# SCH_PCB-device_2024-08-05.net
KiCad netlist of a schematic drawn in EasyEDA
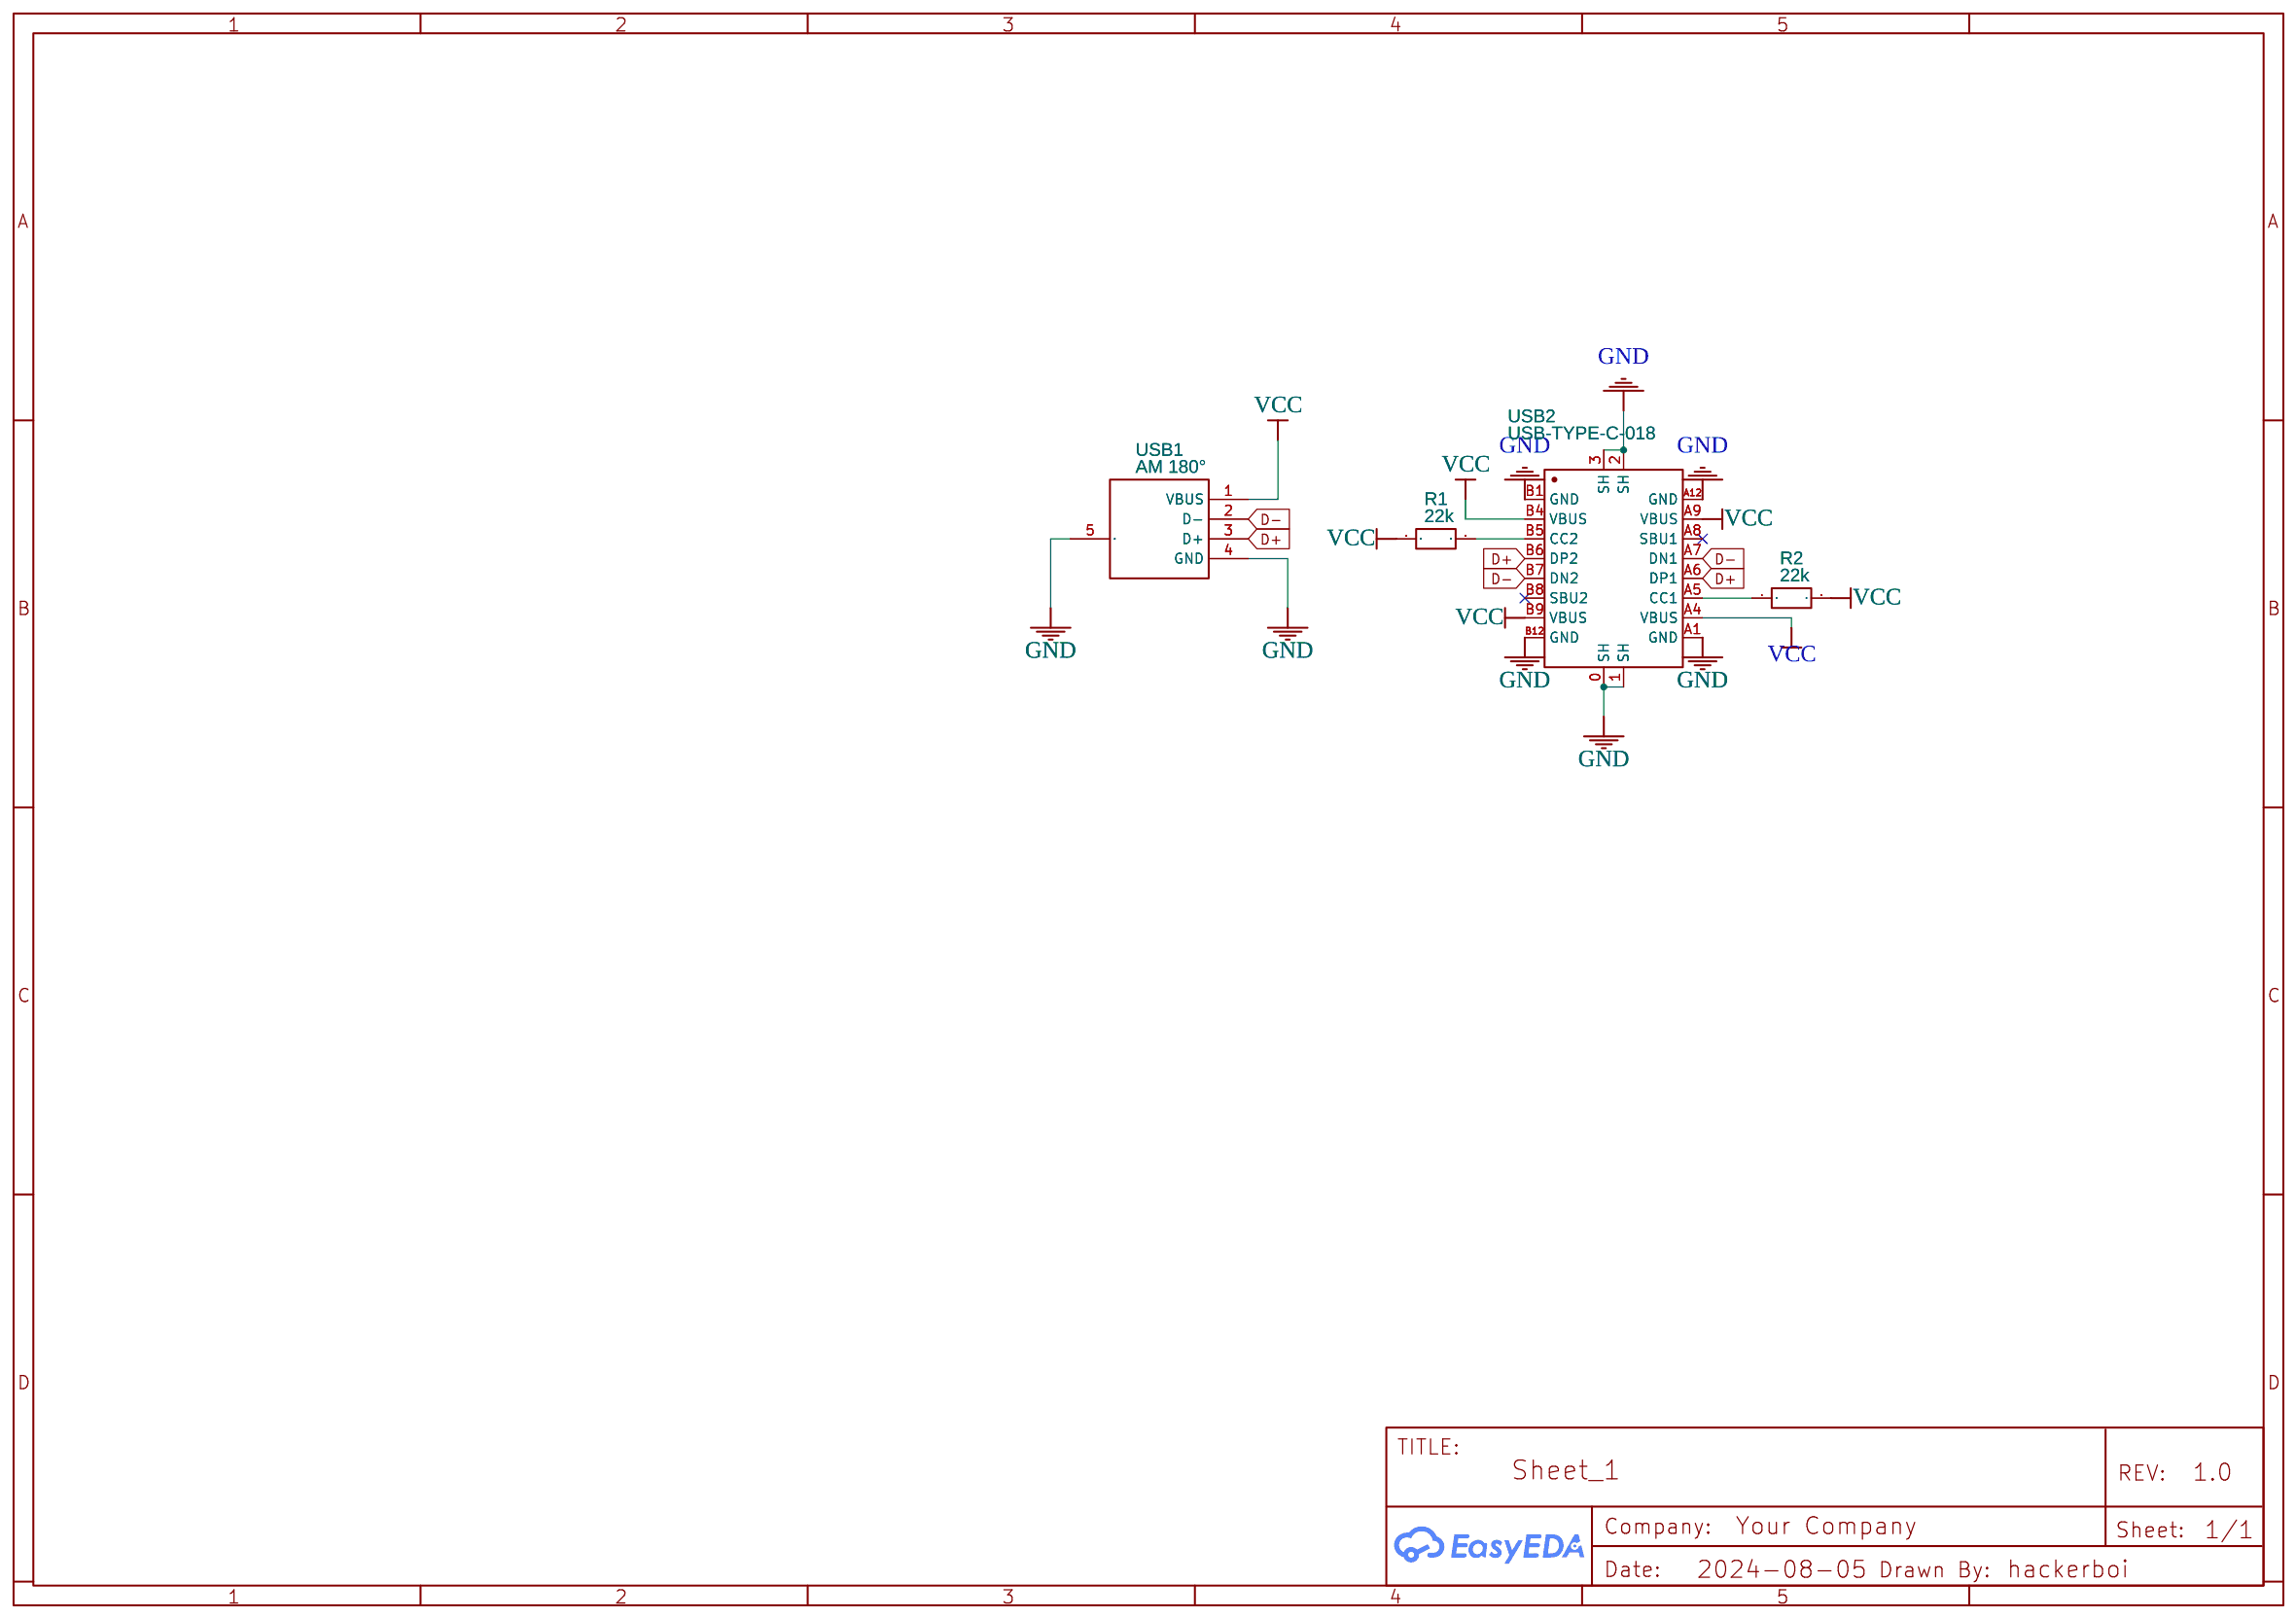
[diagram p0: schematic sheet]

(export (version "E")
  (design (tool "Eeschema 10.0.6"))
  (components
    (comp (ref "R1") (value "22k") (libsource (lib "") (part "R_0603_EU")))
    (comp (ref "R2") (value "22k") (libsource (lib "") (part "R_0603_EU")))
    (comp (ref "USB1")
      (value "AM 180°")
      (fields (field (name "Manufacturer") "SHOU HAN(首韩)"))
      (libsource (lib "") (part "AM 180°"))
    )
    (comp (ref "USB2")
      (value "USB-TYPE-C-018")
      (fields (field (name "Manufacturer") "DEALON(德艺隆)"))
      (libsource (lib "") (part "USB-TYPE-C-018"))
    )
  )
  (nets
    (net (code "1") (name "D+") (class "Default")
      (node (ref "USB1") (pin "3") (pinfunction "D+_3") (pintype "input"))
      (node (ref "USB2") (pin "A6") (pinfunction "DP1_A6") (pintype "unspecified"))
      (node (ref "USB2") (pin "B6") (pinfunction "DP2_B6") (pintype "unspecified"))
    )
    (net (code "2") (name "D-") (class "Default")
      (node (ref "USB1") (pin "2") (pinfunction "D-_2") (pintype "input"))
      (node (ref "USB2") (pin "A7") (pinfunction "DN1_A7") (pintype "unspecified"))
      (node (ref "USB2") (pin "B7") (pinfunction "DN2_B7") (pintype "unspecified"))
    )
    (net (code "3") (name "GND") (class "Default")
      (node (ref "USB1") (pin "4") (pinfunction "GND_4") (pintype "input"))
      (node (ref "USB1") (pin "5") (pinfunction "EH_5") (pintype "input"))
      (node (ref "USB2") (pin "0") (pinfunction "SH_0") (pintype "unspecified"))
      (node (ref "USB2") (pin "1") (pinfunction "SH_1") (pintype "unspecified"))
      (node (ref "USB2") (pin "2") (pinfunction "SH_2") (pintype "unspecified"))
      (node (ref "USB2") (pin "3") (pinfunction "SH_3") (pintype "unspecified"))
      (node (ref "USB2") (pin "A1") (pinfunction "GND_A1") (pintype "unspecified"))
      (node (ref "USB2") (pin "A12") (pinfunction "GND_A12") (pintype "unspecified"))
      (node (ref "USB2") (pin "B1") (pinfunction "GND_B1") (pintype "unspecified"))
      (node (ref "USB2") (pin "B12") (pinfunction "GND_B12") (pintype "unspecified"))
    )
    (net (code "4") (name "Net-(USB2-CC1)") (class "Default")
      (node (ref "R2") (pin "1") (pinfunction "1_1") (pintype "unspecified"))
      (node (ref "USB2") (pin "A5") (pinfunction "CC1_A5") (pintype "unspecified"))
    )
    (net (code "5") (name "Net-(USB2-CC2)") (class "Default")
      (node (ref "R1") (pin "2") (pinfunction "2_2") (pintype "unspecified"))
      (node (ref "USB2") (pin "B5") (pinfunction "CC2_B5") (pintype "unspecified"))
    )
    (net (code "6") (name "VCC") (class "Default")
      (node (ref "R1") (pin "1") (pinfunction "1_1") (pintype "unspecified"))
      (node (ref "R2") (pin "2") (pinfunction "2_2") (pintype "unspecified"))
      (node (ref "USB1") (pin "1") (pinfunction "VBUS_1") (pintype "input"))
      (node (ref "USB2") (pin "A4") (pinfunction "VBUS_A4") (pintype "unspecified"))
      (node (ref "USB2") (pin "A9") (pinfunction "VBUS_A9") (pintype "unspecified"))
      (node (ref "USB2") (pin "B4") (pinfunction "VBUS_B4") (pintype "unspecified"))
      (node (ref "USB2") (pin "B9") (pinfunction "VBUS_B9") (pintype "unspecified"))
    )
    (net (code "7") (name "unconnected-(USB2-SBU1-PadA8)") (class "Default")
      (node (ref "USB2") (pin "A8") (pinfunction "SBU1_A8") (pintype "unspecified+no_connect"))
    )
    (net (code "8") (name "unconnected-(USB2-SBU2-PadB8)") (class "Default")
      (node (ref "USB2") (pin "B8") (pinfunction "SBU2_B8") (pintype "unspecified+no_connect"))
    )
  )
)
